# SCH_Arduino_uno_r3_THT.net
KiCad netlist of a schematic drawn in Altium Designer
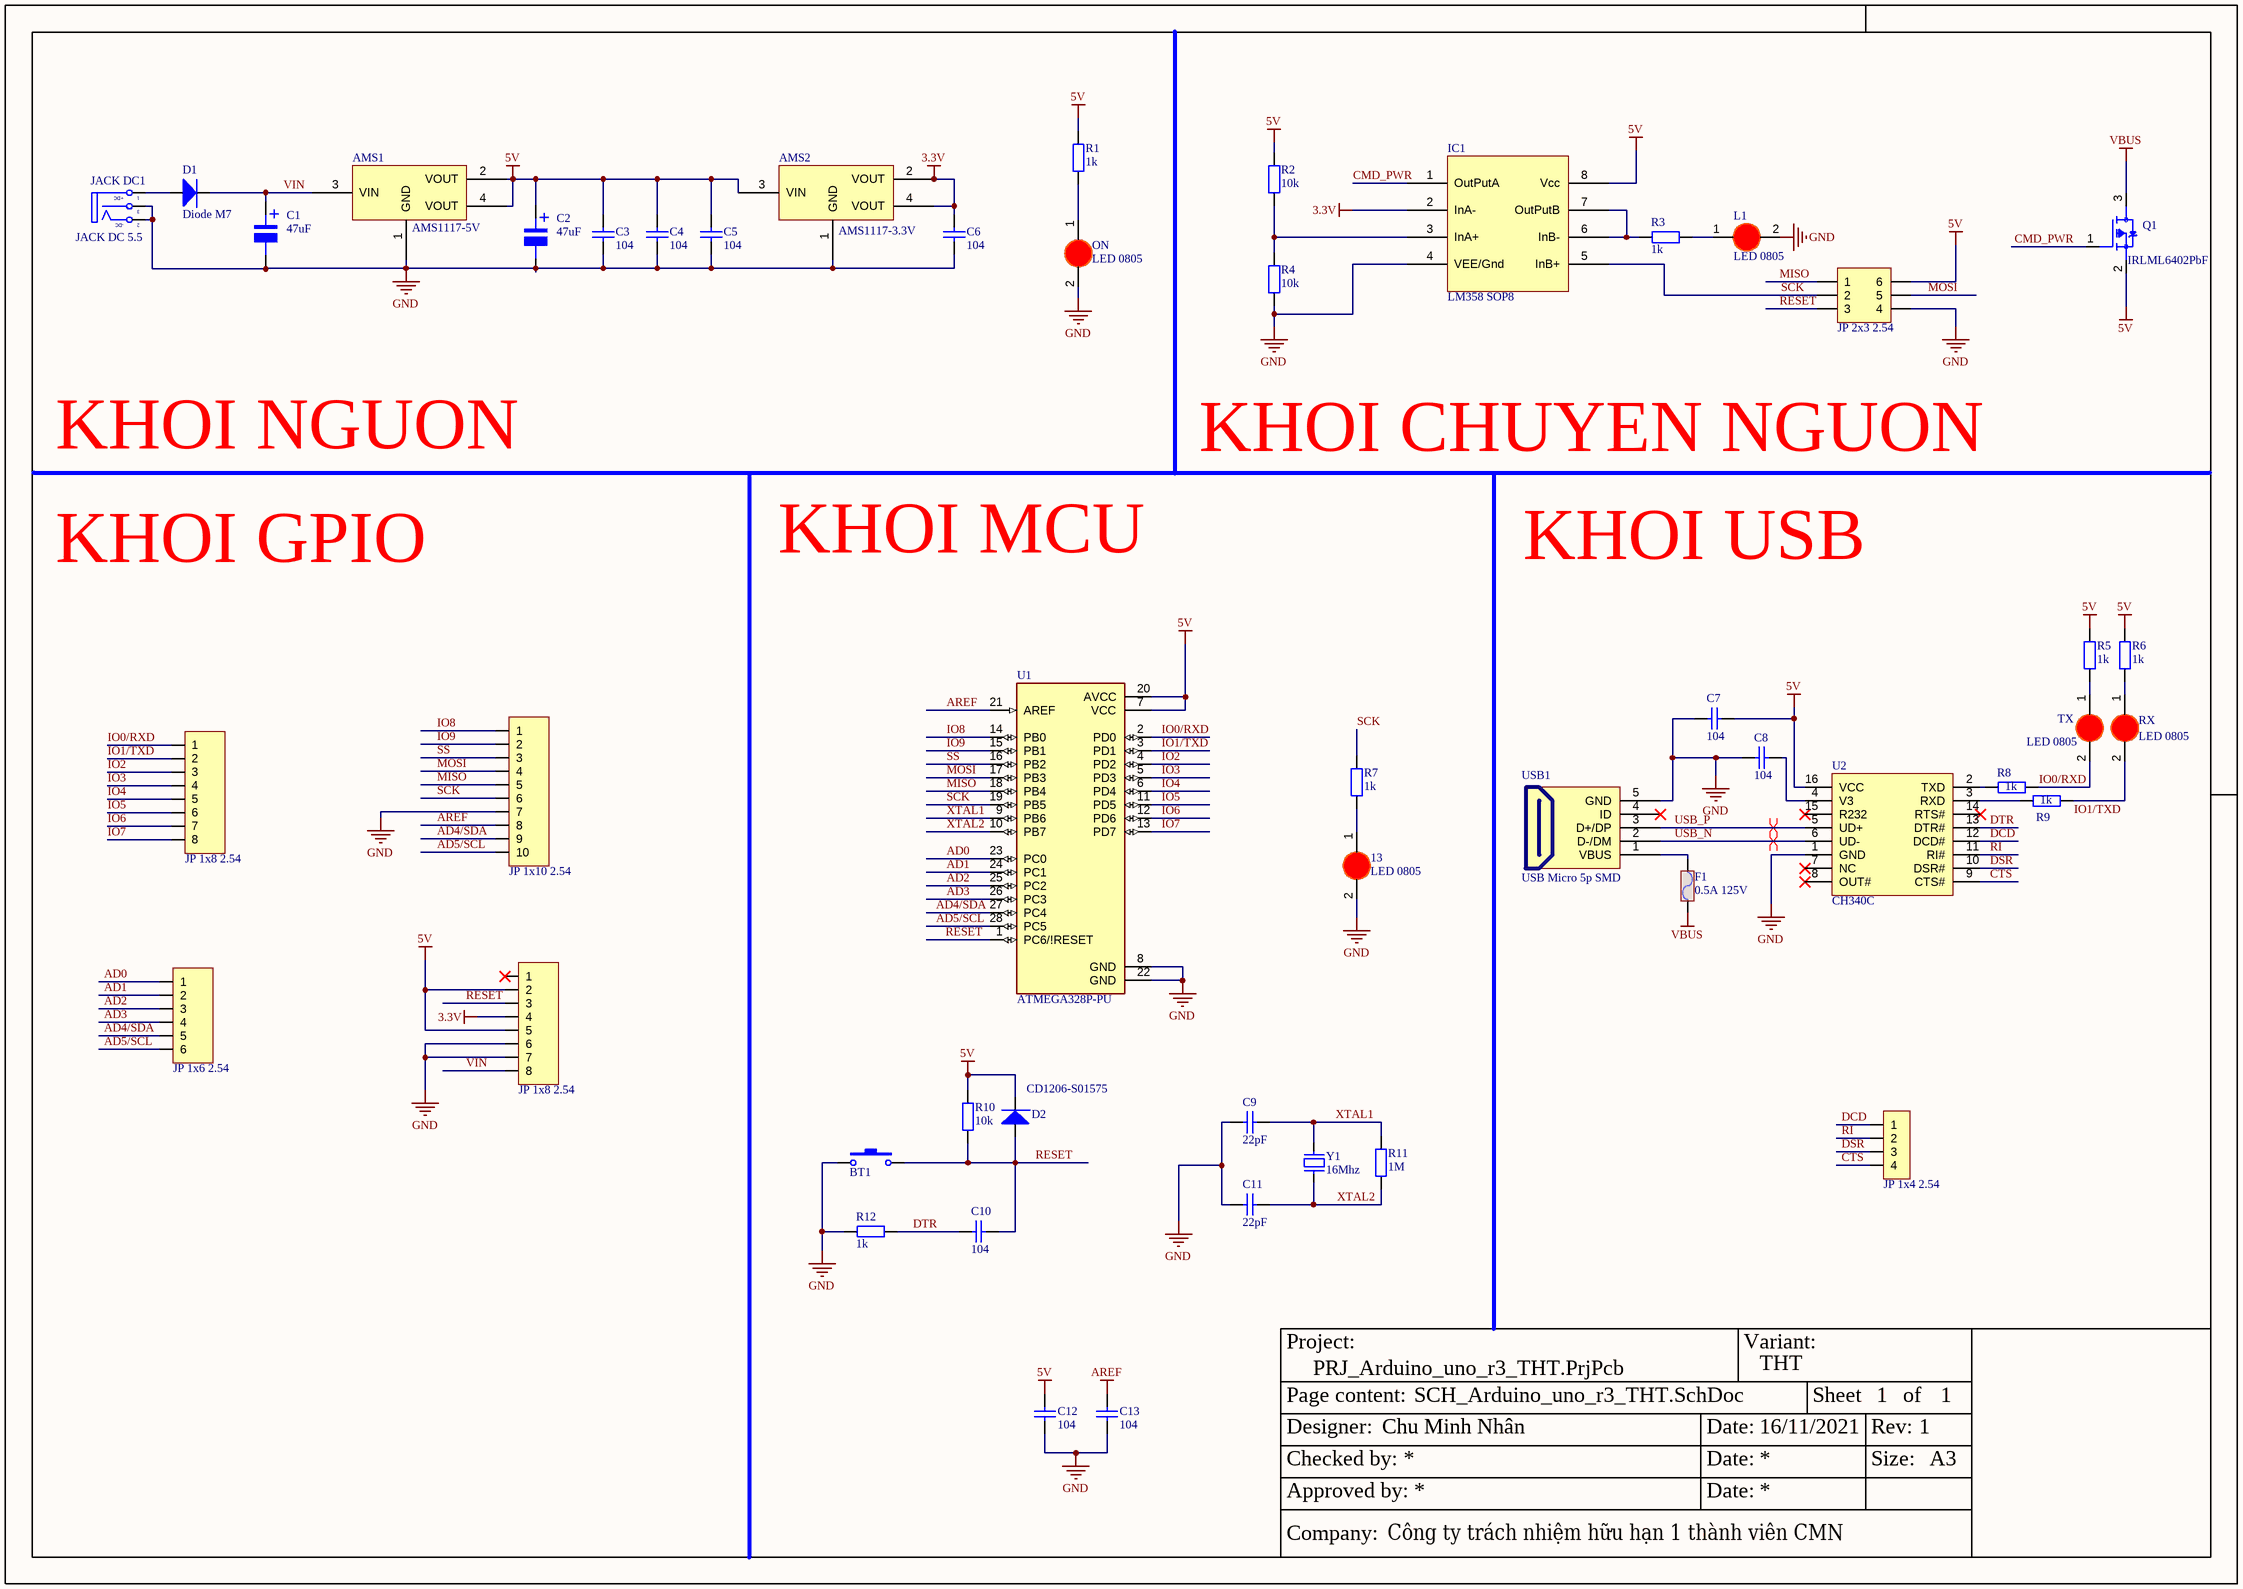
[diagram p0: SCH_Arduino_uno_r3_THT.SchDoc]

(export (version "E")
  (design (tool "Eeschema 10.0.6"))
  (components
    (comp (ref "13")
      (value "LED 0805")
      (footprint "LED-0805-Red")
      (description "Dán")
      (libsource (lib "CMN") (part "LED 0805 Do"))
    )
    (comp (ref "AMS1")
      (value "AMS1117-5V")
      (footprint "SOT223")
      (description "Dán")
      (libsource (lib "CMN") (part "AMS1117_5V SMD"))
    )
    (comp (ref "AMS2")
      (value "AMS1117-3.3V")
      (footprint "SOT223")
      (description "Dán")
      (libsource (lib "CMN") (part "AMS1117_3V3 SMD"))
    )
    (comp (ref "BT1")
      (value "Nut Nhan 2 Chan SMD 3x6x2.5")
      (footprint "Nut Nhan 2 Chan SMD 3x6x2.5")
      (libsource (lib "CMN") (part "Nut Nhan 2 Chan SMD 3x6x2.5"))
    )
    (comp (ref "C1")
      (value "47uF")
      (footprint "tu nhom 6.3 (d)")
      (description "Dán")
      (libsource (lib "CMN") (part "Tu Nhom 47uF 50V"))
    )
    (comp (ref "C2")
      (value "47uF")
      (footprint "tu nhom 6.3 (d)")
      (description "Dán")
      (libsource (lib "CMN") (part "Tu Nhom 47uF 50V"))
    )
    (comp (ref "C3")
      (value "104")
      (footprint "tu 0805")
      (description "Dán")
      (libsource (lib "CMN") (part "Tu 0805 104 50V 10%"))
    )
    (comp (ref "C4")
      (value "104")
      (footprint "tu 0805")
      (description "Dán")
      (libsource (lib "CMN") (part "Tu 0805 104 50V 10%"))
    )
    (comp (ref "C5")
      (value "104")
      (footprint "tu 0805")
      (description "Dán")
      (libsource (lib "CMN") (part "Tu 0805 104 50V 10%"))
    )
    (comp (ref "C6")
      (value "104")
      (footprint "tu 0805")
      (description "Dán")
      (libsource (lib "CMN") (part "Tu 0805 104 50V 10%"))
    )
    (comp (ref "C7")
      (value "104")
      (footprint "tu 0805")
      (description "Dán")
      (libsource (lib "CMN") (part "Tu 0805 104 50V 10%"))
    )
    (comp (ref "C8")
      (value "104")
      (footprint "tu 0805")
      (description "Dán")
      (libsource (lib "CMN") (part "Tu 0805 104 50V 10%"))
    )
    (comp (ref "C9")
      (value "22pF")
      (footprint "tu 0805")
      (description "Dán")
      (libsource (lib "CMN") (part "Tu 0805 22pF 50V 10%"))
    )
    (comp (ref "C10")
      (value "104")
      (footprint "tu 0805")
      (description "Dán")
      (libsource (lib "CMN") (part "Tu 0805 104 50V 10%"))
    )
    (comp (ref "C11")
      (value "22pF")
      (footprint "tu 0805")
      (description "Dán")
      (libsource (lib "CMN") (part "Tu 0805 22pF 50V 10%"))
    )
    (comp (ref "C12")
      (value "104")
      (footprint "tu 0805")
      (description "Dán")
      (libsource (lib "CMN") (part "Tu 0805 104 50V 10%"))
    )
    (comp (ref "C13")
      (value "104")
      (footprint "tu 0805")
      (description "Dán")
      (libsource (lib "CMN") (part "Tu 0805 104 50V 10%"))
    )
    (comp (ref "D1")
      (value "Diode M7")
      (footprint "Diode M7")
      (description "Diode Standard 100V 150mA Surface Mount 1206 (1N4007)")
      (fields (field (name "MP") "CD1206-S01575") (field (name "MF") "Bourns"))
      (libsource (lib "CMN") (part "Diode M7"))
    )
    (comp (ref "D2")
      (value "CD1206-S01575")
      (footprint "CD1206-S01575")
      (description "Diode Standard 100V 150mA Surface Mount 1206")
      (fields (field (name "MF") "Bourns"))
      (libsource (lib "CMN") (part "CD1206-S01575"))
    )
    (comp (ref "F1")
      (value "0.5A 125V")
      (footprint "Cau Chi SMD1808")
      (description "Cau chi 0.5A 125V SMD1808")
      (libsource (lib "CMN") (part "Cau chi 0.5A 125V SMD1808"))
    )
    (comp (ref "IC1")
      (value "LM358 SOP8")
      (footprint "SOP 8")
      (description "Dán")
      (libsource (lib "CMN") (part "LM358 SOP8"))
    )
    (comp (ref "JACK DC1")
      (value "JACK DC 5.5")
      (footprint "JACK DC 5.5")
      (libsource (lib "CMN") (part "JACK DC 5.5"))
    )
    (comp (ref "JP1")
      (value "JP 2x3 2.54")
      (footprint "JP 2x3 DT - duplicate")
      (description "Cắm")
      (libsource (lib "CMN") (part "JP 2x3 2.54 Duc Thang"))
    )
    (comp (ref "JP2")
      (value "JP 1x10 2.54")
      (footprint "JP 1x10 CT")
      (description "Cắm")
      (libsource (lib "CMN") (part "JP 1x10 2.54 Cai Thang"))
    )
    (comp (ref "JP3")
      (value "JP 1x8 2.54")
      (footprint "JP 1x8 CT")
      (description "Cắm")
      (libsource (lib "CMN") (part "JP 1x8 2.54 Cai Thang"))
    )
    (comp (ref "JP4")
      (value "JP 1x8 2.54")
      (footprint "JP 1x8 CT")
      (description "Cắm")
      (libsource (lib "CMN") (part "JP 1x8 2.54 Cai Thang"))
    )
    (comp (ref "JP5")
      (value "JP 1x6 2.54")
      (footprint "JP 1x6 CT")
      (description "Cắm")
      (libsource (lib "CMN") (part "JP 1x6 2.54 Cai Thang"))
    )
    (comp (ref "JP6")
      (value "JP 1x4 2.54")
      (footprint "JP 1x4 DT - duplicate")
      (description "Cắm")
      (libsource (lib "CMN") (part "JP 1x4 2.54 Duc Thang"))
    )
    (comp (ref "L1")
      (value "LED 0805")
      (footprint "LED-0805-Red")
      (description "Dán")
      (libsource (lib "CMN") (part "LED 0805 Do"))
    )
    (comp (ref "ON")
      (value "LED 0805")
      (footprint "LED-0805-Red")
      (description "Dán")
      (libsource (lib "CMN") (part "LED 0805 Do"))
    )
    (comp (ref "Q1")
      (value "IRLML6402PbF")
      (footprint "SOT23_1")
      (description "MOSFET P-Channel 20V 3.7A SOT-23")
      (libsource (lib "CMN") (part "IRLML6402PbF"))
    )
    (comp (ref "R1")
      (value "1k")
      (footprint "tro smd 0805")
      (description "Dán")
      (libsource (lib "CMN") (part "Tro 0805 5% 1k"))
    )
    (comp (ref "R2")
      (value "10k")
      (footprint "tro smd 0805")
      (description "Dán")
      (libsource (lib "CMN") (part "Tro 0805 5% 10k"))
    )
    (comp (ref "R3")
      (value "1k")
      (footprint "tro smd 0805")
      (description "Dán")
      (libsource (lib "CMN") (part "Tro 0805 5% 1k"))
    )
    (comp (ref "R4")
      (value "10k")
      (footprint "tro smd 0805")
      (description "Dán")
      (libsource (lib "CMN") (part "Tro 0805 5% 10k"))
    )
    (comp (ref "R5")
      (value "1k")
      (footprint "tro smd 0805")
      (description "Dán")
      (libsource (lib "CMN") (part "Tro 0805 5% 1k"))
    )
    (comp (ref "R6")
      (value "1k")
      (footprint "tro smd 0805")
      (description "Dán")
      (libsource (lib "CMN") (part "Tro 0805 5% 1k"))
    )
    (comp (ref "R7")
      (value "1k")
      (footprint "tro smd 0805")
      (description "Dán")
      (libsource (lib "CMN") (part "Tro 0805 5% 1k"))
    )
    (comp (ref "R8")
      (value "1k")
      (footprint "tro smd 0805")
      (description "Dán")
      (libsource (lib "CMN") (part "Tro 0805 5% 1k"))
    )
    (comp (ref "R9")
      (value "1k")
      (footprint "tro smd 0805")
      (description "Dán")
      (libsource (lib "CMN") (part "Tro 0805 5% 1k"))
    )
    (comp (ref "R10")
      (value "10k")
      (footprint "tro smd 0805")
      (description "Dán")
      (libsource (lib "CMN") (part "Tro 0805 5% 10k"))
    )
    (comp (ref "R11")
      (value "1M")
      (footprint "tro smd 0805")
      (description "Dán")
      (libsource (lib "CMN") (part "Tro 0805 5% 1M"))
    )
    (comp (ref "R12")
      (value "1k")
      (footprint "tro smd 0805")
      (description "Dán")
      (libsource (lib "CMN") (part "Tro 0805 5% 1k"))
    )
    (comp (ref "RX")
      (value "LED 0805")
      (footprint "LED-0805-Red")
      (description "Dán")
      (libsource (lib "CMN") (part "LED 0805 Do"))
    )
    (comp (ref "TX")
      (value "LED 0805")
      (footprint "LED-0805-Red")
      (description "Dán")
      (libsource (lib "CMN") (part "LED 0805 Do"))
    )
    (comp (ref "U1")
      (value "ATMEGA328P-PU")
      (footprint "28 SPDIP")
      (description "AVR AVRÂ® ATmega Microcontroller IC 8-Bit 20MHz 32KB _16K x 16_ FLASH 28-PDIP")
      (fields (field (name "MF") "Microchip"))
      (libsource (lib "CMN") (part "ATMEGA328P-PU"))
    )
    (comp (ref "U2")
      (value "CH340C")
      (footprint "SOIC16_50_284_25X90_SMT")
      (description "USB Bridge, USB to UART USB 2.0 UART Interface")
      (fields (field (name "MANUFACTURER") "Olimex"))
      (libsource (lib "CMN") (part "CH340C"))
    )
    (comp (ref "USB1")
      (value "USB Micro 5p SMD")
      (footprint "USB Micro 5p SMD")
      (description "USB Type B")
      (libsource (lib "CMN") (part "USB Micro 5p SMD"))
    )
    (comp (ref "Y1")
      (value "16Mhz")
      (footprint "Thach Anh 2 chan SMD")
      (description "Crystal For all Crystal 2pin.")
      (libsource (lib "CMN") (part "Thach Anh 2 chan SMD"))
    )
  )
  (nets
    (net (code "1") (name "/AD0") (class "Default")
      (node (ref "JP5") (pin "1") (pinfunction "1_1") (pintype "passive"))
      (node (ref "U1") (pin "23") (pinfunction "PC0_23") (pintype "bidirectional"))
    )
    (net (code "2") (name "/AD1") (class "Default")
      (node (ref "JP5") (pin "2") (pinfunction "2_2") (pintype "passive"))
      (node (ref "U1") (pin "24") (pinfunction "PC1_24") (pintype "bidirectional"))
    )
    (net (code "3") (name "/AD2") (class "Default")
      (node (ref "JP5") (pin "3") (pinfunction "3_3") (pintype "passive"))
      (node (ref "U1") (pin "25") (pinfunction "PC2_25") (pintype "bidirectional"))
    )
    (net (code "4") (name "/AD3") (class "Default")
      (node (ref "JP5") (pin "4") (pinfunction "4_4") (pintype "passive"))
      (node (ref "U1") (pin "26") (pinfunction "PC3_26") (pintype "bidirectional"))
    )
    (net (code "5") (name "/AD4{slash}SDA") (class "Default")
      (node (ref "JP2") (pin "9") (pinfunction "9_9") (pintype "passive"))
      (node (ref "JP5") (pin "5") (pinfunction "5_5") (pintype "passive"))
      (node (ref "U1") (pin "27") (pinfunction "PC4_27") (pintype "bidirectional"))
    )
    (net (code "6") (name "/AD5{slash}SCL") (class "Default")
      (node (ref "JP2") (pin "10") (pinfunction "10_10") (pintype "passive"))
      (node (ref "JP5") (pin "6") (pinfunction "6_6") (pintype "passive"))
      (node (ref "U1") (pin "28") (pinfunction "PC5_28") (pintype "bidirectional"))
    )
    (net (code "7") (name "/CMD_PWR") (class "Default")
      (node (ref "IC1") (pin "1") (pinfunction "OutPutA_1") (pintype "passive"))
      (node (ref "Q1") (pin "1") (pinfunction "G_1") (pintype "passive"))
    )
    (net (code "8") (name "/CTS") (class "Default")
      (node (ref "JP6") (pin "4") (pinfunction "4_4") (pintype "passive"))
      (node (ref "U2") (pin "9") (pinfunction "CTS#_9") (pintype "passive"))
    )
    (net (code "9") (name "/DCD") (class "Default")
      (node (ref "JP6") (pin "1") (pinfunction "1_1") (pintype "passive"))
      (node (ref "U2") (pin "12") (pinfunction "DCD#_12") (pintype "passive"))
    )
    (net (code "10") (name "/DSR") (class "Default")
      (node (ref "JP6") (pin "3") (pinfunction "3_3") (pintype "passive"))
      (node (ref "U2") (pin "10") (pinfunction "DSR#_10") (pintype "passive"))
    )
    (net (code "11") (name "/DTR") (class "Default")
      (node (ref "C10") (pin "2") (pinfunction "2_2") (pintype "passive"))
      (node (ref "R12") (pin "2") (pinfunction "2_2") (pintype "passive"))
      (node (ref "U2") (pin "13") (pinfunction "DTR#_13") (pintype "passive"))
    )
    (net (code "12") (name "/IO0{slash}RXD") (class "Default")
      (node (ref "JP3") (pin "1") (pinfunction "1_1") (pintype "passive"))
      (node (ref "R8") (pin "1") (pinfunction "1_1") (pintype "passive"))
      (node (ref "TX") (pin "2") (pinfunction "K_2") (pintype "passive"))
      (node (ref "U1") (pin "2") (pinfunction "PD0_2") (pintype "bidirectional"))
    )
    (net (code "13") (name "/IO1{slash}TXD") (class "Default")
      (node (ref "JP3") (pin "2") (pinfunction "2_2") (pintype "passive"))
      (node (ref "R9") (pin "1") (pinfunction "1_1") (pintype "passive"))
      (node (ref "RX") (pin "2") (pinfunction "K_2") (pintype "passive"))
      (node (ref "U1") (pin "3") (pinfunction "PD1_3") (pintype "bidirectional"))
    )
    (net (code "14") (name "/IO2") (class "Default")
      (node (ref "JP3") (pin "3") (pinfunction "3_3") (pintype "passive"))
      (node (ref "U1") (pin "4") (pinfunction "PD2_4") (pintype "bidirectional"))
    )
    (net (code "15") (name "/IO3") (class "Default")
      (node (ref "JP3") (pin "4") (pinfunction "4_4") (pintype "passive"))
      (node (ref "U1") (pin "5") (pinfunction "PD3_5") (pintype "bidirectional"))
    )
    (net (code "16") (name "/IO4") (class "Default")
      (node (ref "JP3") (pin "5") (pinfunction "5_5") (pintype "passive"))
      (node (ref "U1") (pin "6") (pinfunction "PD4_6") (pintype "bidirectional"))
    )
    (net (code "17") (name "/IO5") (class "Default")
      (node (ref "JP3") (pin "6") (pinfunction "6_6") (pintype "passive"))
      (node (ref "U1") (pin "11") (pinfunction "PD5_11") (pintype "bidirectional"))
    )
    (net (code "18") (name "/IO6") (class "Default")
      (node (ref "JP3") (pin "7") (pinfunction "7_7") (pintype "passive"))
      (node (ref "U1") (pin "12") (pinfunction "PD6_12") (pintype "bidirectional"))
    )
    (net (code "19") (name "/IO7") (class "Default")
      (node (ref "JP3") (pin "8") (pinfunction "8_8") (pintype "passive"))
      (node (ref "U1") (pin "13") (pinfunction "PD7_13") (pintype "bidirectional"))
    )
    (net (code "20") (name "/IO8") (class "Default")
      (node (ref "JP2") (pin "1") (pinfunction "1_1") (pintype "passive"))
      (node (ref "U1") (pin "14") (pinfunction "PB0_14") (pintype "bidirectional"))
    )
    (net (code "21") (name "/IO9") (class "Default")
      (node (ref "JP2") (pin "2") (pinfunction "2_2") (pintype "passive"))
      (node (ref "U1") (pin "15") (pinfunction "PB1_15") (pintype "bidirectional"))
    )
    (net (code "22") (name "/MISO") (class "Default")
      (node (ref "JP1") (pin "1") (pinfunction "1_1") (pintype "passive"))
      (node (ref "JP2") (pin "5") (pinfunction "5_5") (pintype "passive"))
      (node (ref "U1") (pin "18") (pinfunction "PB4_18") (pintype "bidirectional"))
    )
    (net (code "23") (name "/MOSI") (class "Default")
      (node (ref "JP1") (pin "5") (pinfunction "5_5") (pintype "passive"))
      (node (ref "JP2") (pin "4") (pinfunction "4_4") (pintype "passive"))
      (node (ref "U1") (pin "17") (pinfunction "PB3_17") (pintype "bidirectional"))
    )
    (net (code "24") (name "/RESET") (class "Default")
      (node (ref "BT1") (pin "2") (pinfunction "2_2") (pintype "passive"))
      (node (ref "C10") (pin "1") (pinfunction "1_1") (pintype "passive"))
      (node (ref "D2") (pin "Anode") (pinfunction "Anode_Anode") (pintype "passive"))
      (node (ref "JP1") (pin "3") (pinfunction "3_3") (pintype "passive"))
      (node (ref "JP4") (pin "3") (pinfunction "3_3") (pintype "passive"))
      (node (ref "R10") (pin "1") (pinfunction "1_1") (pintype "passive"))
      (node (ref "U1") (pin "1") (pinfunction "PC6/!RESET_1") (pintype "bidirectional"))
    )
    (net (code "25") (name "/RI") (class "Default")
      (node (ref "JP6") (pin "2") (pinfunction "2_2") (pintype "passive"))
      (node (ref "U2") (pin "11") (pinfunction "RI#_11") (pintype "passive"))
    )
    (net (code "26") (name "/SCK") (class "Default")
      (node (ref "IC1") (pin "5") (pinfunction "InB+_5") (pintype "passive"))
      (node (ref "JP1") (pin "2") (pinfunction "2_2") (pintype "passive"))
      (node (ref "JP2") (pin "6") (pinfunction "6_6") (pintype "passive"))
      (node (ref "R7") (pin "2") (pinfunction "2_2") (pintype "passive"))
      (node (ref "U1") (pin "19") (pinfunction "PB5_19") (pintype "bidirectional"))
    )
    (net (code "27") (name "/SS") (class "Default")
      (node (ref "JP2") (pin "3") (pinfunction "3_3") (pintype "passive"))
      (node (ref "U1") (pin "16") (pinfunction "PB2_16") (pintype "bidirectional"))
    )
    (net (code "28") (name "/USB_N") (class "Default")
      (node (ref "U2") (pin "6") (pinfunction "UD-_6") (pintype "passive"))
      (node (ref "USB1") (pin "2") (pinfunction "D-/DM_2") (pintype "passive"))
    )
    (net (code "29") (name "/USB_P") (class "Default")
      (node (ref "U2") (pin "5") (pinfunction "UD+_5") (pintype "passive"))
      (node (ref "USB1") (pin "3") (pinfunction "D+/DP_3") (pintype "passive"))
    )
    (net (code "30") (name "/VIN") (class "Default")
      (node (ref "AMS1") (pin "3") (pinfunction "VIN_3") (pintype "passive"))
      (node (ref "C1") (pin "1") (pinfunction "1_1") (pintype "passive"))
      (node (ref "D1") (pin "Cathode") (pinfunction "Cathode_Cathode") (pintype "passive"))
      (node (ref "JP4") (pin "8") (pinfunction "8_8") (pintype "passive"))
    )
    (net (code "31") (name "/XTAL1") (class "Default")
      (node (ref "C9") (pin "1") (pinfunction "1_1") (pintype "passive"))
      (node (ref "R11") (pin "2") (pinfunction "2_2") (pintype "passive"))
      (node (ref "U1") (pin "9") (pinfunction "PB6_9") (pintype "bidirectional"))
      (node (ref "Y1") (pin "2") (pinfunction "2_2") (pintype "passive"))
    )
    (net (code "32") (name "/XTAL2") (class "Default")
      (node (ref "C11") (pin "1") (pinfunction "1_1") (pintype "passive"))
      (node (ref "R11") (pin "1") (pinfunction "1_1") (pintype "passive"))
      (node (ref "U1") (pin "10") (pinfunction "PB7_10") (pintype "bidirectional"))
      (node (ref "Y1") (pin "1") (pinfunction "1_1") (pintype "passive"))
    )
    (net (code "33") (name "3.3V") (class "Default")
      (node (ref "AMS2") (pin "2") (pinfunction "VOUT_2") (pintype "passive"))
      (node (ref "AMS2") (pin "4") (pinfunction "VOUT_4") (pintype "passive"))
      (node (ref "C6") (pin "1") (pinfunction "1_1") (pintype "passive"))
      (node (ref "IC1") (pin "2") (pinfunction "InA-_2") (pintype "passive"))
      (node (ref "JP4") (pin "4") (pinfunction "4_4") (pintype "passive"))
    )
    (net (code "34") (name "5V") (class "Default")
      (node (ref "AMS1") (pin "2") (pinfunction "VOUT_2") (pintype "passive"))
      (node (ref "AMS1") (pin "4") (pinfunction "VOUT_4") (pintype "passive"))
      (node (ref "AMS2") (pin "3") (pinfunction "VIN_3") (pintype "passive"))
      (node (ref "C12") (pin "2") (pinfunction "2_2") (pintype "passive"))
      (node (ref "C2") (pin "1") (pinfunction "1_1") (pintype "passive"))
      (node (ref "C3") (pin "1") (pinfunction "1_1") (pintype "passive"))
      (node (ref "C4") (pin "1") (pinfunction "1_1") (pintype "passive"))
      (node (ref "C5") (pin "1") (pinfunction "1_1") (pintype "passive"))
      (node (ref "C7") (pin "2") (pinfunction "2_2") (pintype "passive"))
      (node (ref "D2") (pin "Cathode") (pinfunction "Cathode_Cathode") (pintype "passive"))
      (node (ref "IC1") (pin "8") (pinfunction "Vcc_8") (pintype "passive"))
      (node (ref "JP1") (pin "6") (pinfunction "6_6") (pintype "passive"))
      (node (ref "JP4") (pin "2") (pinfunction "2_2") (pintype "passive"))
      (node (ref "JP4") (pin "5") (pinfunction "5_5") (pintype "passive"))
      (node (ref "Q1") (pin "2") (pinfunction "S_2") (pintype "passive"))
      (node (ref "R1") (pin "2") (pinfunction "2_2") (pintype "passive"))
      (node (ref "R10") (pin "2") (pinfunction "2_2") (pintype "passive"))
      (node (ref "R2") (pin "2") (pinfunction "2_2") (pintype "passive"))
      (node (ref "R5") (pin "1") (pinfunction "1_1") (pintype "passive"))
      (node (ref "R6") (pin "1") (pinfunction "1_1") (pintype "passive"))
      (node (ref "U1") (pin "20") (pinfunction "AVCC_20") (pintype "power_in"))
      (node (ref "U1") (pin "7") (pinfunction "VCC_7") (pintype "power_in"))
      (node (ref "U2") (pin "16") (pinfunction "VCC_16") (pintype "passive"))
    )
    (net (code "35") (name "AREF") (class "Default")
      (node (ref "C13") (pin "2") (pinfunction "2_2") (pintype "passive"))
      (node (ref "JP2") (pin "8") (pinfunction "8_8") (pintype "passive"))
      (node (ref "U1") (pin "21") (pinfunction "AREF_21") (pintype "input"))
    )
    (net (code "36") (name "GND") (class "Default")
      (node (ref "13") (pin "2") (pinfunction "K_2") (pintype "passive"))
      (node (ref "AMS1") (pin "1") (pinfunction "GND_1") (pintype "passive"))
      (node (ref "AMS2") (pin "1") (pinfunction "GND_1") (pintype "passive"))
      (node (ref "BT1") (pin "1") (pinfunction "1_1") (pintype "passive"))
      (node (ref "C1") (pin "2") (pinfunction "2_2") (pintype "passive"))
      (node (ref "C11") (pin "2") (pinfunction "2_2") (pintype "passive"))
      (node (ref "C12") (pin "1") (pinfunction "1_1") (pintype "passive"))
      (node (ref "C13") (pin "1") (pinfunction "1_1") (pintype "passive"))
      (node (ref "C2") (pin "2") (pinfunction "2_2") (pintype "passive"))
      (node (ref "C3") (pin "2") (pinfunction "2_2") (pintype "passive"))
      (node (ref "C4") (pin "2") (pinfunction "2_2") (pintype "passive"))
      (node (ref "C5") (pin "2") (pinfunction "2_2") (pintype "passive"))
      (node (ref "C6") (pin "2") (pinfunction "2_2") (pintype "passive"))
      (node (ref "C7") (pin "1") (pinfunction "1_1") (pintype "passive"))
      (node (ref "C8") (pin "1") (pinfunction "1_1") (pintype "passive"))
      (node (ref "C9") (pin "2") (pinfunction "2_2") (pintype "passive"))
      (node (ref "IC1") (pin "4") (pinfunction "VEE/Gnd_4") (pintype "passive"))
      (node (ref "JACK DC1") (pin "2") (pinfunction "TN_2") (pintype "passive"))
      (node (ref "JACK DC1") (pin "3") (pinfunction "S_3") (pintype "power_in"))
      (node (ref "JP1") (pin "4") (pinfunction "4_4") (pintype "passive"))
      (node (ref "JP2") (pin "7") (pinfunction "7_7") (pintype "passive"))
      (node (ref "JP4") (pin "6") (pinfunction "6_6") (pintype "passive"))
      (node (ref "JP4") (pin "7") (pinfunction "7_7") (pintype "passive"))
      (node (ref "L1") (pin "2") (pinfunction "K_2") (pintype "passive"))
      (node (ref "ON") (pin "2") (pinfunction "K_2") (pintype "passive"))
      (node (ref "R12") (pin "1") (pinfunction "1_1") (pintype "passive"))
      (node (ref "R4") (pin "1") (pinfunction "1_1") (pintype "passive"))
      (node (ref "U1") (pin "22") (pinfunction "GND_22") (pintype "power_in"))
      (node (ref "U1") (pin "8") (pinfunction "GND_8") (pintype "power_in"))
      (node (ref "U2") (pin "1") (pinfunction "GND_1") (pintype "passive"))
      (node (ref "USB1") (pin "5") (pinfunction "GND_5") (pintype "passive"))
    )
    (net (code "37") (name "Net-(13-A)") (class "Default")
      (node (ref "13") (pin "1") (pinfunction "A_1") (pintype "passive"))
      (node (ref "R7") (pin "1") (pinfunction "1_1") (pintype "passive"))
    )
    (net (code "38") (name "Net-(IC1-InA+)") (class "Default")
      (node (ref "IC1") (pin "3") (pinfunction "InA+_3") (pintype "passive"))
      (node (ref "R2") (pin "1") (pinfunction "1_1") (pintype "passive"))
      (node (ref "R4") (pin "2") (pinfunction "2_2") (pintype "passive"))
    )
    (net (code "39") (name "Net-(IC1-InB-)") (class "Default")
      (node (ref "IC1") (pin "6") (pinfunction "InB-_6") (pintype "passive"))
      (node (ref "IC1") (pin "7") (pinfunction "OutPutB_7") (pintype "passive"))
      (node (ref "R3") (pin "2") (pinfunction "2_2") (pintype "passive"))
    )
    (net (code "40") (name "Net-(JACK DC1-T)") (class "Default")
      (node (ref "D1") (pin "Anode") (pinfunction "Anode_Anode") (pintype "passive"))
      (node (ref "JACK DC1") (pin "1") (pinfunction "T_1") (pintype "passive"))
    )
    (net (code "41") (name "Net-(L1-A)") (class "Default")
      (node (ref "L1") (pin "1") (pinfunction "A_1") (pintype "passive"))
      (node (ref "R3") (pin "1") (pinfunction "1_1") (pintype "passive"))
    )
    (net (code "42") (name "Net-(ON-A)") (class "Default")
      (node (ref "ON") (pin "1") (pinfunction "A_1") (pintype "passive"))
      (node (ref "R1") (pin "1") (pinfunction "1_1") (pintype "passive"))
    )
    (net (code "43") (name "Net-(RX-A)") (class "Default")
      (node (ref "R6") (pin "2") (pinfunction "2_2") (pintype "passive"))
      (node (ref "RX") (pin "1") (pinfunction "A_1") (pintype "passive"))
    )
    (net (code "44") (name "Net-(TX-A)") (class "Default")
      (node (ref "R5") (pin "2") (pinfunction "2_2") (pintype "passive"))
      (node (ref "TX") (pin "1") (pinfunction "A_1") (pintype "passive"))
    )
    (net (code "45") (name "Net-(U2-RXD)") (class "Default")
      (node (ref "R9") (pin "2") (pinfunction "2_2") (pintype "passive"))
      (node (ref "U2") (pin "3") (pinfunction "RXD_3") (pintype "passive"))
    )
    (net (code "46") (name "Net-(U2-TXD)") (class "Default")
      (node (ref "R8") (pin "2") (pinfunction "2_2") (pintype "passive"))
      (node (ref "U2") (pin "2") (pinfunction "TXD_2") (pintype "passive"))
    )
    (net (code "47") (name "Net-(U2-V3)") (class "Default")
      (node (ref "C8") (pin "2") (pinfunction "2_2") (pintype "passive"))
      (node (ref "U2") (pin "4") (pinfunction "V3_4") (pintype "passive"))
    )
    (net (code "48") (name "Net-(USB1-VBUS)") (class "Default")
      (node (ref "F1") (pin "2") (pinfunction "2_2") (pintype "passive"))
      (node (ref "USB1") (pin "1") (pinfunction "VBUS_1") (pintype "passive"))
    )
    (net (code "49") (name "VBUS") (class "Default")
      (node (ref "F1") (pin "1") (pinfunction "1_1") (pintype "passive"))
      (node (ref "Q1") (pin "3") (pinfunction "D_3") (pintype "passive"))
    )
    (net (code "50") (name "unconnected-(JP4-Pad1)") (class "Default")
      (node (ref "JP4") (pin "1") (pinfunction "1_1") (pintype "passive+no_connect"))
    )
    (net (code "51") (name "unconnected-(U2-NC-Pad7)") (class "Default")
      (node (ref "U2") (pin "7") (pinfunction "NC_7") (pintype "passive+no_connect"))
    )
    (net (code "52") (name "unconnected-(U2-OUT#-Pad8)") (class "Default")
      (node (ref "U2") (pin "8") (pinfunction "OUT#_8") (pintype "passive+no_connect"))
    )
    (net (code "53") (name "unconnected-(U2-R232-Pad15)") (class "Default")
      (node (ref "U2") (pin "15") (pinfunction "R232_15") (pintype "passive+no_connect"))
    )
    (net (code "54") (name "unconnected-(U2-RTS#-Pad14)") (class "Default")
      (node (ref "U2") (pin "14") (pinfunction "RTS#_14") (pintype "passive+no_connect"))
    )
    (net (code "55") (name "unconnected-(USB1-ID-Pad4)") (class "Default")
      (node (ref "USB1") (pin "4") (pinfunction "ID_4") (pintype "passive+no_connect"))
    )
  )
)
